# POWER.net
KiCad netlist of a schematic drawn in Altium Designer
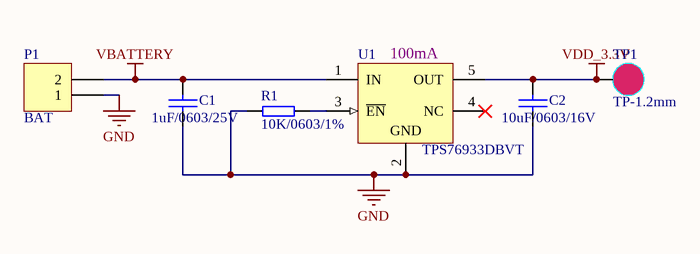
[diagram p0: POWER.SchDoc]

(export (version "E")
  (design (tool "Eeschema 10.0.6"))
  (components
    (comp (ref "C1")
      (value "1uF/0603/25V")
      (footprint "0603")
      (description "Capacitor")
      (libsource (lib "*") (part "CAP"))
    )
    (comp (ref "C2")
      (value "10uF/0603/16V")
      (footprint "0603")
      (description "Capacitor")
      (libsource (lib "*") (part "CAP"))
    )
    (comp (ref "P1")
      (value "BAT")
      (footprint "白色连接器2.54")
      (description "Header, 2-Pin")
      (fields (field (name "PUBLISHER") "Altium Limited"))
      (libsource (lib "Miscellaneous Connectors") (part "Header 2"))
    )
    (comp (ref "R1") (value "10K/0603/1%") (footprint "0603") (libsource (lib "*") (part "RES")))
    (comp (ref "TP1") (value "TP-1.2mm") (footprint "TP-1.2mm") (libsource (lib "LTD") (part "TP-1.2mm")))
    (comp (ref "U1")
      (value "TPS76933DBVT")
      (footprint "TI-DBV5_N")
      (fields (field (name "MANUFACTURER") "Texas Instruments"))
      (libsource (lib "TI Power Management Linear Regulator Single Channel LDO (0-350mA)") (part "TPS76933DBVT"))
    )
  )
  (nets
    (net (code "1") (name "GND") (class "Default")
      (node (ref "C1") (pin "2") (pinfunction "2_2") (pintype "passive"))
      (node (ref "C2") (pin "2") (pinfunction "2_2") (pintype "passive"))
      (node (ref "P1") (pin "1") (pinfunction "1_1") (pintype "passive"))
      (node (ref "R1") (pin "1") (pinfunction "1_1") (pintype "passive"))
      (node (ref "U1") (pin "2") (pinfunction "GND_2") (pintype "power_in"))
    )
    (net (code "2") (name "Net-(U1-~{EN})") (class "Default")
      (node (ref "R1") (pin "2") (pinfunction "2_2") (pintype "passive"))
      (node (ref "U1") (pin "3") (pinfunction "~{EN}_3") (pintype "input"))
    )
    (net (code "3") (name "VBATTERY") (class "Default")
      (node (ref "C1") (pin "1") (pinfunction "1_1") (pintype "passive"))
      (node (ref "P1") (pin "2") (pinfunction "2_2") (pintype "passive"))
      (node (ref "U1") (pin "1") (pinfunction "IN_1") (pintype "power_in"))
    )
    (net (code "4") (name "VDD_3.3V") (class "Default")
      (node (ref "C2") (pin "1") (pinfunction "1_1") (pintype "passive"))
      (node (ref "TP1") (pin "1") (pinfunction "1_1") (pintype "passive"))
      (node (ref "U1") (pin "5") (pinfunction "OUT_5") (pintype "power_in"))
    )
    (net (code "5") (name "unconnected-(U1-NC-Pad4)") (class "Default")
      (node (ref "U1") (pin "4") (pinfunction "NC_4") (pintype "passive+no_connect"))
    )
  )
)
